# GPSClockISAsmd.net
KiCad netlist of a schematic drawn in EAGLE
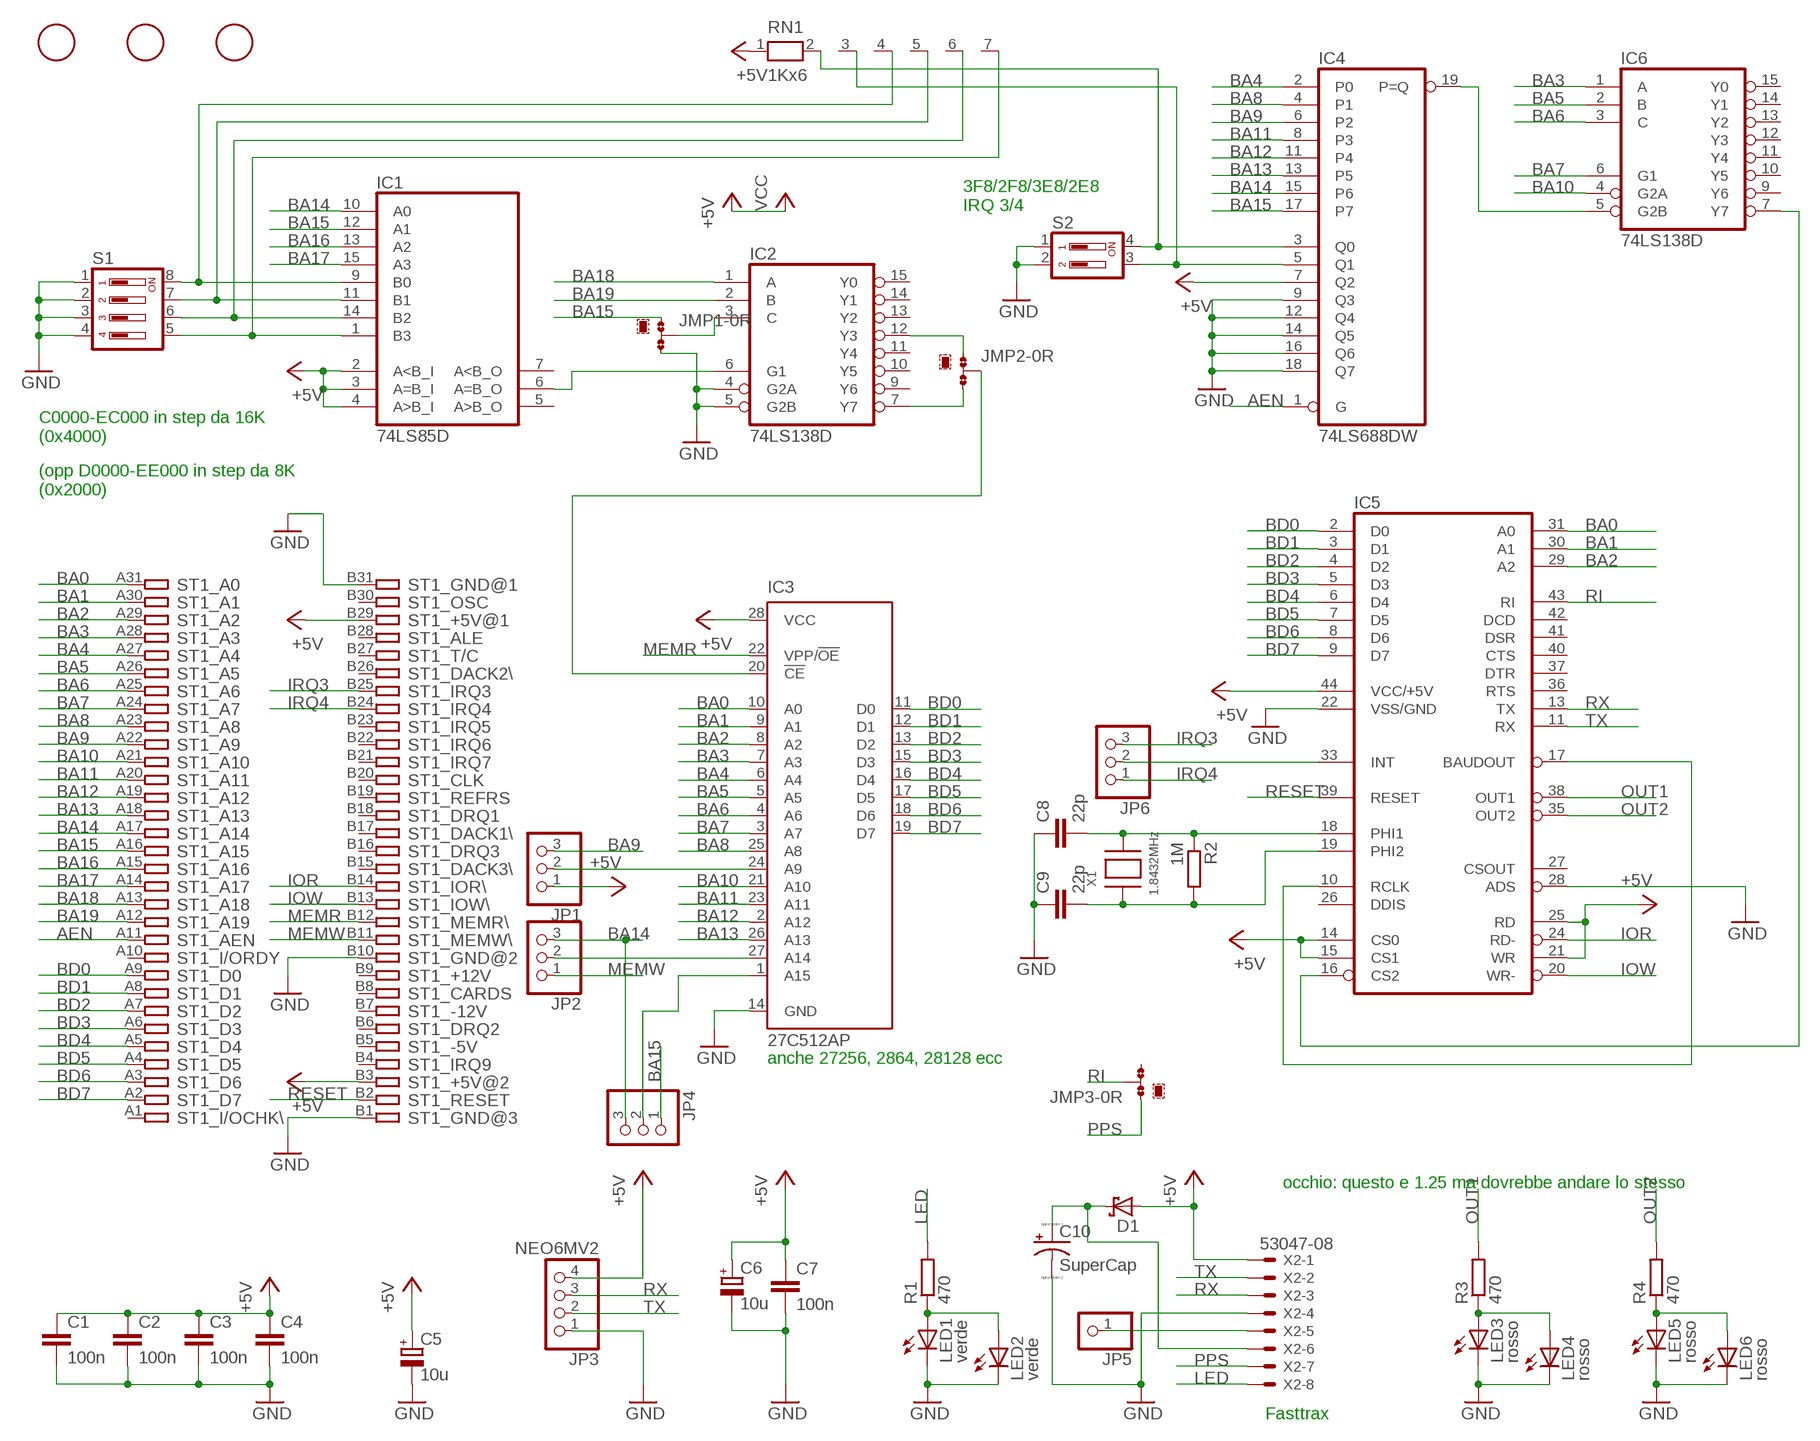
[diagram p0: schematic, sheet 1]

(export (version "E")
  (design (tool "Eeschema 10.0.6"))
  (components
    (comp (ref "C1")
      (value "100n")
      (footprint "eagle-import:C0805")
      (libsource (lib "eagle-import") (part "C-EUC0805"))
    )
    (comp (ref "C2")
      (value "100n")
      (footprint "eagle-import:C0805")
      (libsource (lib "eagle-import") (part "C-EUC0805"))
    )
    (comp (ref "C3")
      (value "100n")
      (footprint "eagle-import:C0805")
      (libsource (lib "eagle-import") (part "C-EUC0805"))
    )
    (comp (ref "C4")
      (value "100n")
      (footprint "eagle-import:C0805")
      (libsource (lib "eagle-import") (part "C-EUC0805"))
    )
    (comp (ref "C5")
      (value "10u")
      (footprint "eagle-import:SMC_D")
      (libsource (lib "eagle-import") (part "CPOL-EUSMCD"))
    )
    (comp (ref "C6")
      (value "10u")
      (footprint "eagle-import:SMC_C")
      (libsource (lib "eagle-import") (part "CPOL-EUSMCC"))
    )
    (comp (ref "C7")
      (value "100n")
      (footprint "eagle-import:C0805")
      (libsource (lib "eagle-import") (part "C-EUC0805"))
    )
    (comp (ref "C8")
      (value "22p")
      (footprint "eagle-import:C0805")
      (libsource (lib "eagle-import") (part "C-EUC0805"))
    )
    (comp (ref "C9")
      (value "22p")
      (footprint "eagle-import:C0805")
      (libsource (lib "eagle-import") (part "C-EUC0805"))
    )
    (comp (ref "C10")
      (value "SuperCap")
      (footprint "eagle-import:EB22,5D")
      (libsource (lib "eagle-import") (part "CPOL-USE10-22.5"))
    )
    (comp (ref "D1")
      (value "SCHOTTKY-DIODESMC")
      (footprint "eagle-import:SMC")
      (libsource (lib "eagle-import") (part "SCHOTTKY-DIODESMC"))
    )
    (comp (ref "F1")
      (value "FIDUCIAL")
      (footprint "eagle-import:FIDUCIAL_1MM")
      (libsource (lib "eagle-import") (part "FIDUCIAL"))
    )
    (comp (ref "F2")
      (value "FIDUCIAL")
      (footprint "eagle-import:FIDUCIAL_1MM")
      (libsource (lib "eagle-import") (part "FIDUCIAL"))
    )
    (comp (ref "F3")
      (value "FIDUCIAL")
      (footprint "eagle-import:FIDUCIAL_1MM")
      (libsource (lib "eagle-import") (part "FIDUCIAL"))
    )
    (comp (ref "IC1")
      (value "74LS85D")
      (footprint "eagle-import:SO16")
      (libsource (lib "eagle-import") (part "7485DLS"))
    )
    (comp (ref "IC2")
      (value "74LS138D")
      (footprint "eagle-import:SO16")
      (libsource (lib "eagle-import") (part "74138DLS"))
    )
    (comp (ref "IC3")
      (value "27C512AP")
      (footprint "eagle-import:DIL28-6")
      (fields (field (name "MPN") "M27C512-90B6"))
      (libsource (lib "eagle-import") (part "27512APC"))
    )
    (comp (ref "IC4")
      (value "74LS688DW")
      (footprint "eagle-import:SO20W")
      (libsource (lib "eagle-import") (part "74688DWLS"))
    )
    (comp (ref "IC5")
      (value "8250PLCC")
      (footprint "eagle-import:PLCC44")
      (libsource (lib "eagle-import") (part "8250PLCC"))
    )
    (comp (ref "IC6")
      (value "74LS138D")
      (footprint "eagle-import:SO16")
      (libsource (lib "eagle-import") (part "74138DLS"))
    )
    (comp (ref "JMP1")
      (value "0R-JUMPC")
      (footprint "eagle-import:C0R-JMP")
      (libsource (lib "eagle-import") (part "0R-JUMPC"))
    )
    (comp (ref "JMP2")
      (value "0R-JUMPC")
      (footprint "eagle-import:C0R-JMP")
      (libsource (lib "eagle-import") (part "0R-JUMPC"))
    )
    (comp (ref "JMP3")
      (value "0R-JUMPC")
      (footprint "eagle-import:C0R-JMP")
      (libsource (lib "eagle-import") (part "0R-JUMPC"))
    )
    (comp (ref "JP1")
      (value "PINHD-1X03_2.54")
      (footprint "eagle-import:1X03")
      (libsource (lib "eagle-import") (part "PINHD-1X03_2.54"))
    )
    (comp (ref "JP2")
      (value "PINHD-1X03_2.54")
      (footprint "eagle-import:1X03")
      (libsource (lib "eagle-import") (part "PINHD-1X03_2.54"))
    )
    (comp (ref "JP3")
      (value "NEO6MV2")
      (footprint "eagle-import:1X04")
      (libsource (lib "eagle-import") (part "PINHD-1X4"))
    )
    (comp (ref "JP4")
      (value "PINHD-1X03_2.54")
      (footprint "eagle-import:1X03")
      (libsource (lib "eagle-import") (part "PINHD-1X03_2.54"))
    )
    (comp (ref "JP5")
      (value "PINHD-1X1")
      (footprint "eagle-import:1X01")
      (libsource (lib "eagle-import") (part "PINHD-1X1"))
    )
    (comp (ref "JP6")
      (value "PINHD-1X03_2.54")
      (footprint "eagle-import:1X03")
      (libsource (lib "eagle-import") (part "PINHD-1X03_2.54"))
    )
    (comp (ref "LED1")
      (value "verde")
      (footprint "eagle-import:CHIPLED_0805")
      (libsource (lib "eagle-import") (part "led_LEDCHIPLED_0805"))
    )
    (comp (ref "LED2")
      (value "verde")
      (footprint "eagle-import:LED3MM")
      (libsource (lib "eagle-import") (part "LED3MM"))
    )
    (comp (ref "LED3")
      (value "rosso")
      (footprint "eagle-import:CHIPLED_0805")
      (libsource (lib "eagle-import") (part "led_LEDCHIPLED_0805"))
    )
    (comp (ref "LED4")
      (value "rosso")
      (footprint "eagle-import:LED3MM")
      (libsource (lib "eagle-import") (part "LED3MM"))
    )
    (comp (ref "LED5")
      (value "rosso")
      (footprint "eagle-import:CHIPLED_0805")
      (libsource (lib "eagle-import") (part "led_LEDCHIPLED_0805"))
    )
    (comp (ref "LED6")
      (value "rosso")
      (footprint "eagle-import:LED3MM")
      (libsource (lib "eagle-import") (part "LED3MM"))
    )
    (comp (ref "R1")
      (value "470")
      (footprint "eagle-import:R0805")
      (libsource (lib "eagle-import") (part "R-EU_R0805"))
    )
    (comp (ref "R2")
      (value "1M")
      (footprint "eagle-import:R0805")
      (libsource (lib "eagle-import") (part "R-EU_R0805"))
    )
    (comp (ref "R3")
      (value "470")
      (footprint "eagle-import:R0805")
      (libsource (lib "eagle-import") (part "R-EU_R0805"))
    )
    (comp (ref "R4")
      (value "470")
      (footprint "eagle-import:R0805")
      (libsource (lib "eagle-import") (part "R-EU_R0805"))
    )
    (comp (ref "RN1")
      (value "1Kx6")
      (footprint "eagle-import:RN-7")
      (libsource (lib "eagle-import") (part "RN06"))
    )
    (comp (ref "S1")
      (value "DIP04YL")
      (footprint "eagle-import:DIP04YL")
      (libsource (lib "eagle-import") (part "DIP04YL"))
    )
    (comp (ref "S2")
      (value "DIP02YL")
      (footprint "eagle-import:DIP02YL")
      (libsource (lib "eagle-import") (part "DIP02YL"))
    )
    (comp (ref "ST1")
      (value "IBM8BIT")
      (footprint "eagle-import:IBM8BIT")
      (libsource (lib "eagle-import") (part "IBM8BIT"))
    )
    (comp (ref "X1")
      (value "1.8432MHz")
      (footprint "eagle-import:NX8045")
      (libsource (lib "eagle-import") (part "XTALNX8045"))
    )
    (comp (ref "X2")
      (value "53047-08")
      (footprint "eagle-import:53047-08")
      (fields (field (name "MPN") "53047-0810"))
      (libsource (lib "eagle-import") (part "53?-08047"))
    )
  )
  (nets
    (net (code "1") (name "+5V") (class "Default")
      (node (ref "C1") (pin "1") (pinfunction "1_1") (pintype "passive"))
      (node (ref "C2") (pin "1") (pinfunction "1_1") (pintype "passive"))
      (node (ref "C3") (pin "1") (pinfunction "1_1") (pintype "passive"))
      (node (ref "C4") (pin "1") (pinfunction "1_1") (pintype "passive"))
      (node (ref "C5") (pin "+") (pinfunction "+_+") (pintype "passive"))
      (node (ref "C6") (pin "+") (pinfunction "+_+") (pintype "passive"))
      (node (ref "C7") (pin "1") (pinfunction "1_1") (pintype "passive"))
      (node (ref "D1") (pin "A") (pinfunction "A_A") (pintype "passive"))
      (node (ref "IC1") (pin "2") (pinfunction "A<B_I_2") (pintype "input"))
      (node (ref "IC1") (pin "3") (pinfunction "A=B_I_3") (pintype "input"))
      (node (ref "IC1") (pin "4") (pinfunction "A>B_I_4") (pintype "input"))
      (node (ref "IC3") (pin "28") (pinfunction "VCC_28") (pintype "power_in"))
      (node (ref "IC4") (pin "7") (pinfunction "Q2_7") (pintype "input"))
      (node (ref "IC5") (pin "14") (pinfunction "CS0_14") (pintype "input"))
      (node (ref "IC5") (pin "15") (pinfunction "CS1_15") (pintype "input"))
      (node (ref "IC5") (pin "21") (pinfunction "WR_21") (pintype "input"))
      (node (ref "IC5") (pin "25") (pinfunction "RD_25") (pintype "input"))
      (node (ref "IC5") (pin "44") (pinfunction "VCC/+5V_44") (pintype "power_in"))
      (node (ref "JP1") (pin "1") (pinfunction "1_1") (pintype "passive"))
      (node (ref "JP3") (pin "4") (pinfunction "4_4") (pintype "passive"))
      (node (ref "RN1") (pin "1") (pinfunction "1_1") (pintype "passive"))
      (node (ref "ST1") (pin "B29") (pinfunction "P_B29") (pintype "bidirectional"))
      (node (ref "ST1") (pin "B3") (pinfunction "P_B3") (pintype "bidirectional"))
      (node (ref "X2") (pin "1") (pinfunction "S_1") (pintype "passive"))
    )
    (net (code "2") (name "/AEN") (class "Default")
      (node (ref "IC4") (pin "1") (pinfunction "G_1") (pintype "input"))
      (node (ref "ST1") (pin "A11") (pinfunction "P_A11") (pintype "bidirectional"))
    )
    (net (code "3") (name "/BA0") (class "Default")
      (node (ref "IC3") (pin "10") (pinfunction "A0_10") (pintype "input"))
      (node (ref "IC5") (pin "31") (pinfunction "A0_31") (pintype "input"))
      (node (ref "ST1") (pin "A31") (pinfunction "P_A31") (pintype "bidirectional"))
    )
    (net (code "4") (name "/BA1") (class "Default")
      (node (ref "IC3") (pin "9") (pinfunction "A1_9") (pintype "input"))
      (node (ref "IC5") (pin "30") (pinfunction "A1_30") (pintype "input"))
      (node (ref "ST1") (pin "A30") (pinfunction "P_A30") (pintype "bidirectional"))
    )
    (net (code "5") (name "/BA2") (class "Default")
      (node (ref "IC3") (pin "8") (pinfunction "A2_8") (pintype "input"))
      (node (ref "IC5") (pin "29") (pinfunction "A2_29") (pintype "input"))
      (node (ref "ST1") (pin "A29") (pinfunction "P_A29") (pintype "bidirectional"))
    )
    (net (code "6") (name "/BA3") (class "Default")
      (node (ref "IC3") (pin "7") (pinfunction "A3_7") (pintype "input"))
      (node (ref "IC6") (pin "1") (pinfunction "A_1") (pintype "input"))
      (node (ref "ST1") (pin "A28") (pinfunction "P_A28") (pintype "bidirectional"))
    )
    (net (code "7") (name "/BA4") (class "Default")
      (node (ref "IC3") (pin "6") (pinfunction "A4_6") (pintype "input"))
      (node (ref "IC4") (pin "2") (pinfunction "P0_2") (pintype "input"))
      (node (ref "ST1") (pin "A27") (pinfunction "P_A27") (pintype "bidirectional"))
    )
    (net (code "8") (name "/BA5") (class "Default")
      (node (ref "IC3") (pin "5") (pinfunction "A5_5") (pintype "input"))
      (node (ref "IC6") (pin "2") (pinfunction "B_2") (pintype "input"))
      (node (ref "ST1") (pin "A26") (pinfunction "P_A26") (pintype "bidirectional"))
    )
    (net (code "9") (name "/BA6") (class "Default")
      (node (ref "IC3") (pin "4") (pinfunction "A6_4") (pintype "input"))
      (node (ref "IC6") (pin "3") (pinfunction "C_3") (pintype "input"))
      (node (ref "ST1") (pin "A25") (pinfunction "P_A25") (pintype "bidirectional"))
    )
    (net (code "10") (name "/BA7") (class "Default")
      (node (ref "IC3") (pin "3") (pinfunction "A7_3") (pintype "input"))
      (node (ref "IC6") (pin "6") (pinfunction "G1_6") (pintype "input"))
      (node (ref "ST1") (pin "A24") (pinfunction "P_A24") (pintype "bidirectional"))
    )
    (net (code "11") (name "/BA8") (class "Default")
      (node (ref "IC3") (pin "25") (pinfunction "A8_25") (pintype "input"))
      (node (ref "IC4") (pin "4") (pinfunction "P1_4") (pintype "input"))
      (node (ref "ST1") (pin "A23") (pinfunction "P_A23") (pintype "bidirectional"))
    )
    (net (code "12") (name "/BA9") (class "Default")
      (node (ref "IC4") (pin "6") (pinfunction "P2_6") (pintype "input"))
      (node (ref "JP1") (pin "3") (pinfunction "3_3") (pintype "passive"))
      (node (ref "ST1") (pin "A22") (pinfunction "P_A22") (pintype "bidirectional"))
    )
    (net (code "13") (name "/BA10") (class "Default")
      (node (ref "IC3") (pin "21") (pinfunction "A10_21") (pintype "input"))
      (node (ref "IC6") (pin "4") (pinfunction "G2A_4") (pintype "input"))
      (node (ref "ST1") (pin "A21") (pinfunction "P_A21") (pintype "bidirectional"))
    )
    (net (code "14") (name "/BA11") (class "Default")
      (node (ref "IC3") (pin "23") (pinfunction "A11_23") (pintype "input"))
      (node (ref "IC4") (pin "8") (pinfunction "P3_8") (pintype "input"))
      (node (ref "ST1") (pin "A20") (pinfunction "P_A20") (pintype "bidirectional"))
    )
    (net (code "15") (name "/BA12") (class "Default")
      (node (ref "IC3") (pin "2") (pinfunction "A12_2") (pintype "input"))
      (node (ref "IC4") (pin "11") (pinfunction "P4_11") (pintype "input"))
      (node (ref "ST1") (pin "A19") (pinfunction "P_A19") (pintype "bidirectional"))
    )
    (net (code "16") (name "/BA13") (class "Default")
      (node (ref "IC3") (pin "26") (pinfunction "A13_26") (pintype "input"))
      (node (ref "IC4") (pin "13") (pinfunction "P5_13") (pintype "input"))
      (node (ref "ST1") (pin "A18") (pinfunction "P_A18") (pintype "bidirectional"))
    )
    (net (code "17") (name "/BA14") (class "Default")
      (node (ref "IC1") (pin "10") (pinfunction "A0_10") (pintype "input"))
      (node (ref "IC4") (pin "15") (pinfunction "P6_15") (pintype "input"))
      (node (ref "JP2") (pin "3") (pinfunction "3_3") (pintype "passive"))
      (node (ref "JP4") (pin "3") (pinfunction "3_3") (pintype "passive"))
      (node (ref "ST1") (pin "A17") (pinfunction "P_A17") (pintype "bidirectional"))
    )
    (net (code "18") (name "/BA15") (class "Default")
      (node (ref "IC1") (pin "12") (pinfunction "A1_12") (pintype "input"))
      (node (ref "IC4") (pin "17") (pinfunction "P7_17") (pintype "input"))
      (node (ref "JMP1") (pin "1") (pinfunction "1_1") (pintype "passive"))
      (node (ref "JP4") (pin "1") (pinfunction "1_1") (pintype "passive"))
      (node (ref "ST1") (pin "A16") (pinfunction "P_A16") (pintype "bidirectional"))
    )
    (net (code "19") (name "/BA16") (class "Default")
      (node (ref "IC1") (pin "13") (pinfunction "A2_13") (pintype "input"))
      (node (ref "ST1") (pin "A15") (pinfunction "P_A15") (pintype "bidirectional"))
    )
    (net (code "20") (name "/BA17") (class "Default")
      (node (ref "IC1") (pin "15") (pinfunction "A3_15") (pintype "input"))
      (node (ref "ST1") (pin "A14") (pinfunction "P_A14") (pintype "bidirectional"))
    )
    (net (code "21") (name "/BA18") (class "Default")
      (node (ref "IC2") (pin "1") (pinfunction "A_1") (pintype "input"))
      (node (ref "ST1") (pin "A13") (pinfunction "P_A13") (pintype "bidirectional"))
    )
    (net (code "22") (name "/BA19") (class "Default")
      (node (ref "IC2") (pin "2") (pinfunction "B_2") (pintype "input"))
      (node (ref "ST1") (pin "A12") (pinfunction "P_A12") (pintype "bidirectional"))
    )
    (net (code "23") (name "/BD0") (class "Default")
      (node (ref "IC3") (pin "11") (pinfunction "D0_11") (pintype "tri_state"))
      (node (ref "IC5") (pin "2") (pinfunction "D0_2") (pintype "bidirectional"))
      (node (ref "ST1") (pin "A9") (pinfunction "P_A9") (pintype "bidirectional"))
    )
    (net (code "24") (name "/BD1") (class "Default")
      (node (ref "IC3") (pin "12") (pinfunction "D1_12") (pintype "tri_state"))
      (node (ref "IC5") (pin "3") (pinfunction "D1_3") (pintype "bidirectional"))
      (node (ref "ST1") (pin "A8") (pinfunction "P_A8") (pintype "bidirectional"))
    )
    (net (code "25") (name "/BD2") (class "Default")
      (node (ref "IC3") (pin "13") (pinfunction "D2_13") (pintype "tri_state"))
      (node (ref "IC5") (pin "4") (pinfunction "D2_4") (pintype "bidirectional"))
      (node (ref "ST1") (pin "A7") (pinfunction "P_A7") (pintype "bidirectional"))
    )
    (net (code "26") (name "/BD3") (class "Default")
      (node (ref "IC3") (pin "15") (pinfunction "D3_15") (pintype "tri_state"))
      (node (ref "IC5") (pin "5") (pinfunction "D3_5") (pintype "bidirectional"))
      (node (ref "ST1") (pin "A6") (pinfunction "P_A6") (pintype "bidirectional"))
    )
    (net (code "27") (name "/BD4") (class "Default")
      (node (ref "IC3") (pin "16") (pinfunction "D4_16") (pintype "tri_state"))
      (node (ref "IC5") (pin "6") (pinfunction "D4_6") (pintype "bidirectional"))
      (node (ref "ST1") (pin "A5") (pinfunction "P_A5") (pintype "bidirectional"))
    )
    (net (code "28") (name "/BD5") (class "Default")
      (node (ref "IC3") (pin "17") (pinfunction "D5_17") (pintype "tri_state"))
      (node (ref "IC5") (pin "7") (pinfunction "D5_7") (pintype "bidirectional"))
      (node (ref "ST1") (pin "A4") (pinfunction "P_A4") (pintype "bidirectional"))
    )
    (net (code "29") (name "/BD6") (class "Default")
      (node (ref "IC3") (pin "18") (pinfunction "D6_18") (pintype "tri_state"))
      (node (ref "IC5") (pin "8") (pinfunction "D6_8") (pintype "bidirectional"))
      (node (ref "ST1") (pin "A3") (pinfunction "P_A3") (pintype "bidirectional"))
    )
    (net (code "30") (name "/BD7") (class "Default")
      (node (ref "IC3") (pin "19") (pinfunction "D7_19") (pintype "tri_state"))
      (node (ref "IC5") (pin "9") (pinfunction "D7_9") (pintype "bidirectional"))
      (node (ref "ST1") (pin "A2") (pinfunction "P_A2") (pintype "bidirectional"))
    )
    (net (code "31") (name "/IOR") (class "Default")
      (node (ref "IC5") (pin "24") (pinfunction "RD-_24") (pintype "input"))
      (node (ref "ST1") (pin "B14") (pinfunction "P_B14") (pintype "bidirectional"))
    )
    (net (code "32") (name "/IOW") (class "Default")
      (node (ref "IC5") (pin "20") (pinfunction "WR-_20") (pintype "input"))
      (node (ref "ST1") (pin "B13") (pinfunction "P_B13") (pintype "bidirectional"))
    )
    (net (code "33") (name "/IRQ3") (class "Default")
      (node (ref "JP6") (pin "3") (pinfunction "3_3") (pintype "passive"))
      (node (ref "ST1") (pin "B25") (pinfunction "P_B25") (pintype "bidirectional"))
    )
    (net (code "34") (name "/IRQ4") (class "Default")
      (node (ref "JP6") (pin "1") (pinfunction "1_1") (pintype "passive"))
      (node (ref "ST1") (pin "B24") (pinfunction "P_B24") (pintype "bidirectional"))
    )
    (net (code "35") (name "/LED") (class "Default")
      (node (ref "R1") (pin "2") (pinfunction "2_2") (pintype "passive"))
      (node (ref "X2") (pin "8") (pinfunction "S_8") (pintype "passive"))
    )
    (net (code "36") (name "/MEMR") (class "Default")
      (node (ref "IC3") (pin "22") (pinfunction "VPP/~{OE}_22") (pintype "input"))
      (node (ref "ST1") (pin "B12") (pinfunction "P_B12") (pintype "bidirectional"))
    )
    (net (code "37") (name "/MEMW") (class "Default")
      (node (ref "JP2") (pin "1") (pinfunction "1_1") (pintype "passive"))
      (node (ref "ST1") (pin "B11") (pinfunction "P_B11") (pintype "bidirectional"))
    )
    (net (code "38") (name "/OUT1") (class "Default")
      (node (ref "IC5") (pin "38") (pinfunction "OUT1_38") (pintype "input"))
      (node (ref "R3") (pin "2") (pinfunction "2_2") (pintype "passive"))
    )
    (net (code "39") (name "/OUT2") (class "Default")
      (node (ref "IC5") (pin "35") (pinfunction "OUT2_35") (pintype "input"))
      (node (ref "R4") (pin "2") (pinfunction "2_2") (pintype "passive"))
    )
    (net (code "40") (name "/PPS") (class "Default")
      (node (ref "JMP3") (pin "1") (pinfunction "1_1") (pintype "passive"))
      (node (ref "X2") (pin "7") (pinfunction "S_7") (pintype "passive"))
    )
    (net (code "41") (name "/RESET") (class "Default")
      (node (ref "IC5") (pin "39") (pinfunction "RESET_39") (pintype "input"))
      (node (ref "ST1") (pin "B2") (pinfunction "P_B2") (pintype "bidirectional"))
    )
    (net (code "42") (name "/RI") (class "Default")
      (node (ref "IC5") (pin "43") (pinfunction "RI_43") (pintype "output"))
      (node (ref "JMP3") (pin "2") (pinfunction "2_2") (pintype "passive"))
    )
    (net (code "43") (name "/RX") (class "Default")
      (node (ref "IC5") (pin "13") (pinfunction "TX_13") (pintype "output"))
      (node (ref "JP3") (pin "3") (pinfunction "3_3") (pintype "passive"))
      (node (ref "X2") (pin "3") (pinfunction "S_3") (pintype "passive"))
    )
    (net (code "44") (name "/TX") (class "Default")
      (node (ref "IC5") (pin "11") (pinfunction "RX_11") (pintype "input"))
      (node (ref "JP3") (pin "2") (pinfunction "2_2") (pintype "passive"))
      (node (ref "X2") (pin "2") (pinfunction "S_2") (pintype "passive"))
    )
    (net (code "45") (name "GND") (class "Default")
      (node (ref "C1") (pin "2") (pinfunction "2_2") (pintype "passive"))
      (node (ref "C10") (pin "-") (pinfunction "-_-") (pintype "passive"))
      (node (ref "C2") (pin "2") (pinfunction "2_2") (pintype "passive"))
      (node (ref "C3") (pin "2") (pinfunction "2_2") (pintype "passive"))
      (node (ref "C4") (pin "2") (pinfunction "2_2") (pintype "passive"))
      (node (ref "C5") (pin "-") (pinfunction "-_-") (pintype "passive"))
      (node (ref "C6") (pin "-") (pinfunction "-_-") (pintype "passive"))
      (node (ref "C7") (pin "2") (pinfunction "2_2") (pintype "passive"))
      (node (ref "C8") (pin "1") (pinfunction "1_1") (pintype "passive"))
      (node (ref "C9") (pin "1") (pinfunction "1_1") (pintype "passive"))
      (node (ref "IC2") (pin "4") (pinfunction "G2A_4") (pintype "input"))
      (node (ref "IC2") (pin "5") (pinfunction "G2B_5") (pintype "input"))
      (node (ref "IC3") (pin "14") (pinfunction "GND_14") (pintype "power_in"))
      (node (ref "IC4") (pin "12") (pinfunction "Q4_12") (pintype "input"))
      (node (ref "IC4") (pin "14") (pinfunction "Q5_14") (pintype "input"))
      (node (ref "IC4") (pin "16") (pinfunction "Q6_16") (pintype "input"))
      (node (ref "IC4") (pin "18") (pinfunction "Q7_18") (pintype "input"))
      (node (ref "IC4") (pin "9") (pinfunction "Q3_9") (pintype "input"))
      (node (ref "IC5") (pin "22") (pinfunction "VSS/GND_22") (pintype "power_in"))
      (node (ref "IC5") (pin "28") (pinfunction "ADS_28") (pintype "input"))
      (node (ref "JMP1") (pin "3") (pinfunction "3_3") (pintype "passive"))
      (node (ref "JP3") (pin "1") (pinfunction "1_1") (pintype "passive"))
      (node (ref "LED1") (pin "C") (pinfunction "C_C") (pintype "passive"))
      (node (ref "LED2") (pin "K") (pinfunction "C_K") (pintype "passive"))
      (node (ref "LED3") (pin "C") (pinfunction "C_C") (pintype "passive"))
      (node (ref "LED4") (pin "K") (pinfunction "C_K") (pintype "passive"))
      (node (ref "LED5") (pin "C") (pinfunction "C_C") (pintype "passive"))
      (node (ref "LED6") (pin "K") (pinfunction "C_K") (pintype "passive"))
      (node (ref "S1") (pin "1") (pinfunction "1_1") (pintype "passive"))
      (node (ref "S1") (pin "2") (pinfunction "2_2") (pintype "passive"))
      (node (ref "S1") (pin "3") (pinfunction "3_3") (pintype "passive"))
      (node (ref "S1") (pin "4") (pinfunction "4_4") (pintype "passive"))
      (node (ref "S2") (pin "1") (pinfunction "1_1") (pintype "passive"))
      (node (ref "S2") (pin "2") (pinfunction "2_2") (pintype "passive"))
      (node (ref "ST1") (pin "B1") (pinfunction "P_B1") (pintype "bidirectional"))
      (node (ref "ST1") (pin "B10") (pinfunction "P_B10") (pintype "bidirectional"))
      (node (ref "ST1") (pin "B31") (pinfunction "P_B31") (pintype "bidirectional"))
      (node (ref "X2") (pin "4") (pinfunction "S_4") (pintype "passive"))
    )
    (net (code "46") (name "Net-(IC1A-A=B_O)") (class "Default")
      (node (ref "IC1") (pin "6") (pinfunction "A=B_O_6") (pintype "output"))
      (node (ref "IC2") (pin "6") (pinfunction "G1_6") (pintype "input"))
    )
    (net (code "47") (name "Net-(IC1A-B0)") (class "Default")
      (node (ref "IC1") (pin "9") (pinfunction "B0_9") (pintype "input"))
      (node (ref "RN1") (pin "4") (pinfunction "4_4") (pintype "passive"))
      (node (ref "S1") (pin "8") (pinfunction "8_8") (pintype "passive"))
    )
    (net (code "48") (name "Net-(IC1A-B1)") (class "Default")
      (node (ref "IC1") (pin "11") (pinfunction "B1_11") (pintype "input"))
      (node (ref "RN1") (pin "5") (pinfunction "5_5") (pintype "passive"))
      (node (ref "S1") (pin "7") (pinfunction "7_7") (pintype "passive"))
    )
    (net (code "49") (name "Net-(IC1A-B2)") (class "Default")
      (node (ref "IC1") (pin "14") (pinfunction "B2_14") (pintype "input"))
      (node (ref "RN1") (pin "6") (pinfunction "6_6") (pintype "passive"))
      (node (ref "S1") (pin "6") (pinfunction "6_6") (pintype "passive"))
    )
    (net (code "50") (name "Net-(IC1A-B3)") (class "Default")
      (node (ref "IC1") (pin "1") (pinfunction "B3_1") (pintype "input"))
      (node (ref "RN1") (pin "7") (pinfunction "7_7") (pintype "passive"))
      (node (ref "S1") (pin "5") (pinfunction "5_5") (pintype "passive"))
    )
    (net (code "51") (name "Net-(IC2A-C)") (class "Default")
      (node (ref "IC2") (pin "3") (pinfunction "C_3") (pintype "input"))
      (node (ref "JMP1") (pin "2") (pinfunction "2_2") (pintype "passive"))
    )
    (net (code "52") (name "Net-(IC2A-Y3)") (class "Default")
      (node (ref "IC2") (pin "12") (pinfunction "Y3_12") (pintype "output"))
      (node (ref "JMP2") (pin "1") (pinfunction "1_1") (pintype "passive"))
    )
    (net (code "53") (name "Net-(IC2A-Y7)") (class "Default")
      (node (ref "IC2") (pin "7") (pinfunction "Y7_7") (pintype "output"))
      (node (ref "JMP2") (pin "3") (pinfunction "3_3") (pintype "passive"))
    )
    (net (code "54") (name "Net-(IC3-A9)") (class "Default")
      (node (ref "IC3") (pin "24") (pinfunction "A9_24") (pintype "input"))
      (node (ref "JP1") (pin "2") (pinfunction "2_2") (pintype "passive"))
    )
    (net (code "55") (name "Net-(IC3-A14)") (class "Default")
      (node (ref "IC3") (pin "27") (pinfunction "A14_27") (pintype "input"))
      (node (ref "JP2") (pin "2") (pinfunction "2_2") (pintype "passive"))
    )
    (net (code "56") (name "Net-(IC3-A15)") (class "Default")
      (node (ref "IC3") (pin "1") (pinfunction "A15_1") (pintype "input"))
      (node (ref "JP4") (pin "2") (pinfunction "2_2") (pintype "passive"))
    )
    (net (code "57") (name "Net-(IC3-~{CE})") (class "Default")
      (node (ref "IC3") (pin "20") (pinfunction "~{CE}_20") (pintype "input"))
      (node (ref "JMP2") (pin "2") (pinfunction "2_2") (pintype "passive"))
    )
    (net (code "58") (name "Net-(IC4A-P=Q)") (class "Default")
      (node (ref "IC4") (pin "19") (pinfunction "P=Q_19") (pintype "output"))
      (node (ref "IC6") (pin "5") (pinfunction "G2B_5") (pintype "input"))
    )
    (net (code "59") (name "Net-(IC4A-Q0)") (class "Default")
      (node (ref "IC4") (pin "3") (pinfunction "Q0_3") (pintype "input"))
      (node (ref "RN1") (pin "2") (pinfunction "2_2") (pintype "passive"))
      (node (ref "S2") (pin "4") (pinfunction "4_4") (pintype "passive"))
    )
    (net (code "60") (name "Net-(IC4A-Q1)") (class "Default")
      (node (ref "IC4") (pin "5") (pinfunction "Q1_5") (pintype "input"))
      (node (ref "RN1") (pin "3") (pinfunction "3_3") (pintype "passive"))
      (node (ref "S2") (pin "3") (pinfunction "3_3") (pintype "passive"))
    )
    (net (code "61") (name "Net-(IC5-BAUDOUT)") (class "Default")
      (node (ref "IC5") (pin "10") (pinfunction "RCLK_10") (pintype "input"))
      (node (ref "IC5") (pin "17") (pinfunction "BAUDOUT_17") (pintype "output"))
    )
    (net (code "62") (name "Net-(IC5-CS2)") (class "Default")
      (node (ref "IC5") (pin "16") (pinfunction "CS2_16") (pintype "input"))
      (node (ref "IC6") (pin "7") (pinfunction "Y7_7") (pintype "output"))
    )
    (net (code "63") (name "Net-(IC5-INT)") (class "Default")
      (node (ref "IC5") (pin "33") (pinfunction "INT_33") (pintype "output"))
      (node (ref "JP6") (pin "2") (pinfunction "2_2") (pintype "passive"))
    )
    (net (code "64") (name "Net-(IC5-PHI1)") (class "Default")
      (node (ref "C8") (pin "2") (pinfunction "2_2") (pintype "passive"))
      (node (ref "IC5") (pin "18") (pinfunction "PHI1_18") (pintype "input"))
      (node (ref "R2") (pin "1") (pinfunction "1_1") (pintype "passive"))
      (node (ref "X1") (pin "P$2") (pinfunction "P$2_P$2") (pintype "bidirectional"))
    )
    (net (code "65") (name "Net-(IC5-PHI2)") (class "Default")
      (node (ref "C9") (pin "2") (pinfunction "2_2") (pintype "passive"))
      (node (ref "IC5") (pin "19") (pinfunction "PHI2_19") (pintype "input"))
      (node (ref "R2") (pin "2") (pinfunction "2_2") (pintype "passive"))
      (node (ref "X1") (pin "P$1") (pinfunction "P$1_P$1") (pintype "bidirectional"))
    )
    (net (code "66") (name "Net-(LED1-PadA)") (class "Default")
      (node (ref "LED1") (pin "A") (pinfunction "A_A") (pintype "passive"))
      (node (ref "LED2") (pin "A") (pinfunction "A_A") (pintype "passive"))
      (node (ref "R1") (pin "1") (pinfunction "1_1") (pintype "passive"))
    )
    (net (code "67") (name "Net-(LED3-PadA)") (class "Default")
      (node (ref "LED3") (pin "A") (pinfunction "A_A") (pintype "passive"))
      (node (ref "LED4") (pin "A") (pinfunction "A_A") (pintype "passive"))
      (node (ref "R3") (pin "1") (pinfunction "1_1") (pintype "passive"))
    )
    (net (code "68") (name "Net-(LED5-PadA)") (class "Default")
      (node (ref "LED5") (pin "A") (pinfunction "A_A") (pintype "passive"))
      (node (ref "LED6") (pin "A") (pinfunction "A_A") (pintype "passive"))
      (node (ref "R4") (pin "1") (pinfunction "1_1") (pintype "passive"))
    )
    (net (code "69") (name "Net-(X2E-S)") (class "Default")
      (node (ref "JP5") (pin "1") (pinfunction "1_1") (pintype "passive"))
      (node (ref "X2") (pin "5") (pinfunction "S_5") (pintype "passive"))
    )
    (net (code "70") (name "Net-(X2F-S)") (class "Default")
      (node (ref "C10") (pin "+") (pinfunction "+_+") (pintype "passive"))
      (node (ref "D1") (pin "C") (pinfunction "C_C") (pintype "passive"))
      (node (ref "X2") (pin "6") (pinfunction "S_6") (pintype "passive"))
    )
    (net (code "71") (name "unconnected-(IC1A-A<B_O-Pad7)") (class "Default")
      (node (ref "IC1") (pin "7") (pinfunction "A<B_O_7") (pintype "output"))
    )
    (net (code "72") (name "unconnected-(IC1A-A>B_O-Pad5)") (class "Default")
      (node (ref "IC1") (pin "5") (pinfunction "A>B_O_5") (pintype "output"))
    )
    (net (code "73") (name "unconnected-(IC2A-Y0-Pad15)") (class "Default")
      (node (ref "IC2") (pin "15") (pinfunction "Y0_15") (pintype "output"))
    )
    (net (code "74") (name "unconnected-(IC2A-Y1-Pad14)") (class "Default")
      (node (ref "IC2") (pin "14") (pinfunction "Y1_14") (pintype "output"))
    )
    (net (code "75") (name "unconnected-(IC2A-Y2-Pad13)") (class "Default")
      (node (ref "IC2") (pin "13") (pinfunction "Y2_13") (pintype "output"))
    )
    (net (code "76") (name "unconnected-(IC2A-Y4-Pad11)") (class "Default")
      (node (ref "IC2") (pin "11") (pinfunction "Y4_11") (pintype "output"))
    )
    (net (code "77") (name "unconnected-(IC2A-Y5-Pad10)") (class "Default")
      (node (ref "IC2") (pin "10") (pinfunction "Y5_10") (pintype "output"))
    )
    (net (code "78") (name "unconnected-(IC2A-Y6-Pad9)") (class "Default")
      (node (ref "IC2") (pin "9") (pinfunction "Y6_9") (pintype "output"))
    )
    (net (code "79") (name "unconnected-(IC5-CSOUT-Pad27)") (class "Default")
      (node (ref "IC5") (pin "27") (pinfunction "CSOUT_27") (pintype "output"))
    )
    (net (code "80") (name "unconnected-(IC5-CTS-Pad40)") (class "Default")
      (node (ref "IC5") (pin "40") (pinfunction "CTS_40") (pintype "output"))
    )
    (net (code "81") (name "unconnected-(IC5-DCD-Pad42)") (class "Default")
      (node (ref "IC5") (pin "42") (pinfunction "DCD_42") (pintype "output"))
    )
    (net (code "82") (name "unconnected-(IC5-DDIS-Pad26)") (class "Default")
      (node (ref "IC5") (pin "26") (pinfunction "DDIS_26") (pintype "output"))
    )
    (net (code "83") (name "unconnected-(IC5-DSR-Pad41)") (class "Default")
      (node (ref "IC5") (pin "41") (pinfunction "DSR_41") (pintype "output"))
    )
    (net (code "84") (name "unconnected-(IC5-DTR-Pad37)") (class "Default")
      (node (ref "IC5") (pin "37") (pinfunction "DTR_37") (pintype "output"))
    )
    (net (code "85") (name "unconnected-(IC5-RTS-Pad36)") (class "Default")
      (node (ref "IC5") (pin "36") (pinfunction "RTS_36") (pintype "output"))
    )
    (net (code "86") (name "unconnected-(IC6A-Y0-Pad15)") (class "Default")
      (node (ref "IC6") (pin "15") (pinfunction "Y0_15") (pintype "output"))
    )
    (net (code "87") (name "unconnected-(IC6A-Y1-Pad14)") (class "Default")
      (node (ref "IC6") (pin "14") (pinfunction "Y1_14") (pintype "output"))
    )
    (net (code "88") (name "unconnected-(IC6A-Y2-Pad13)") (class "Default")
      (node (ref "IC6") (pin "13") (pinfunction "Y2_13") (pintype "output"))
    )
    (net (code "89") (name "unconnected-(IC6A-Y3-Pad12)") (class "Default")
      (node (ref "IC6") (pin "12") (pinfunction "Y3_12") (pintype "output"))
    )
    (net (code "90") (name "unconnected-(IC6A-Y4-Pad11)") (class "Default")
      (node (ref "IC6") (pin "11") (pinfunction "Y4_11") (pintype "output"))
    )
    (net (code "91") (name "unconnected-(IC6A-Y5-Pad10)") (class "Default")
      (node (ref "IC6") (pin "10") (pinfunction "Y5_10") (pintype "output"))
    )
    (net (code "92") (name "unconnected-(IC6A-Y6-Pad9)") (class "Default")
      (node (ref "IC6") (pin "9") (pinfunction "Y6_9") (pintype "output"))
    )
    (net (code "93") (name "unconnected-(JMP3-Pad3)") (class "Default")
      (node (ref "JMP3") (pin "3") (pinfunction "3_3") (pintype "passive"))
    )
    (net (code "94") (name "unconnected-(ST1A-P-PadB9)") (class "Default")
      (node (ref "ST1") (pin "B9") (pinfunction "P_B9") (pintype "bidirectional"))
    )
    (net (code "95") (name "unconnected-(ST1AA-P-PadB28)") (class "Default")
      (node (ref "ST1") (pin "B28") (pinfunction "P_B28") (pintype "bidirectional"))
    )
    (net (code "96") (name "unconnected-(ST1AB-P-PadB8)") (class "Default")
      (node (ref "ST1") (pin "B8") (pinfunction "P_B8") (pintype "bidirectional"))
    )
    (net (code "97") (name "unconnected-(ST1AC-P-PadB20)") (class "Default")
      (node (ref "ST1") (pin "B20") (pinfunction "P_B20") (pintype "bidirectional"))
    )
    (net (code "98") (name "unconnected-(ST1AL-P-PadB17)") (class "Default")
      (node (ref "ST1") (pin "B17") (pinfunction "P_B17") (pintype "bidirectional"))
    )
    (net (code "99") (name "unconnected-(ST1AM-P-PadB26)") (class "Default")
      (node (ref "ST1") (pin "B26") (pinfunction "P_B26") (pintype "bidirectional"))
    )
    (net (code "100") (name "unconnected-(ST1AN-P-PadB15)") (class "Default")
      (node (ref "ST1") (pin "B15") (pinfunction "P_B15") (pintype "bidirectional"))
    )
    (net (code "101") (name "unconnected-(ST1AO-P-PadB18)") (class "Default")
      (node (ref "ST1") (pin "B18") (pinfunction "P_B18") (pintype "bidirectional"))
    )
    (net (code "102") (name "unconnected-(ST1AP-P-PadB6)") (class "Default")
      (node (ref "ST1") (pin "B6") (pinfunction "P_B6") (pintype "bidirectional"))
    )
    (net (code "103") (name "unconnected-(ST1AQ-P-PadB16)") (class "Default")
      (node (ref "ST1") (pin "B16") (pinfunction "P_B16") (pintype "bidirectional"))
    )
    (net (code "104") (name "unconnected-(ST1AU-P-PadA1)") (class "Default")
      (node (ref "ST1") (pin "A1") (pinfunction "P_A1") (pintype "bidirectional"))
    )
    (net (code "105") (name "unconnected-(ST1AV-P-PadA10)") (class "Default")
      (node (ref "ST1") (pin "A10") (pinfunction "P_A10") (pintype "bidirectional"))
    )
    (net (code "106") (name "unconnected-(ST1BA-P-PadB23)") (class "Default")
      (node (ref "ST1") (pin "B23") (pinfunction "P_B23") (pintype "bidirectional"))
    )
    (net (code "107") (name "unconnected-(ST1BB-P-PadB22)") (class "Default")
      (node (ref "ST1") (pin "B22") (pinfunction "P_B22") (pintype "bidirectional"))
    )
    (net (code "108") (name "unconnected-(ST1BC-P-PadB21)") (class "Default")
      (node (ref "ST1") (pin "B21") (pinfunction "P_B21") (pintype "bidirectional"))
    )
    (net (code "109") (name "unconnected-(ST1BD-P-PadB4)") (class "Default")
      (node (ref "ST1") (pin "B4") (pinfunction "P_B4") (pintype "bidirectional"))
    )
    (net (code "110") (name "unconnected-(ST1BG-P-PadB30)") (class "Default")
      (node (ref "ST1") (pin "B30") (pinfunction "P_B30") (pintype "bidirectional"))
    )
    (net (code "111") (name "unconnected-(ST1BH-P-PadB19)") (class "Default")
      (node (ref "ST1") (pin "B19") (pinfunction "P_B19") (pintype "bidirectional"))
    )
    (net (code "112") (name "unconnected-(ST1BJ-P-PadB27)") (class "Default")
      (node (ref "ST1") (pin "B27") (pinfunction "P_B27") (pintype "bidirectional"))
    )
    (net (code "113") (name "unconnected-(ST1D-P-PadB7)") (class "Default")
      (node (ref "ST1") (pin "B7") (pinfunction "P_B7") (pintype "bidirectional"))
    )
    (net (code "114") (name "unconnected-(ST1E-P-PadB5)") (class "Default")
      (node (ref "ST1") (pin "B5") (pinfunction "P_B5") (pintype "bidirectional"))
    )
  )
)
